# Input.net
KiCad netlist of a schematic drawn in Altium Designer
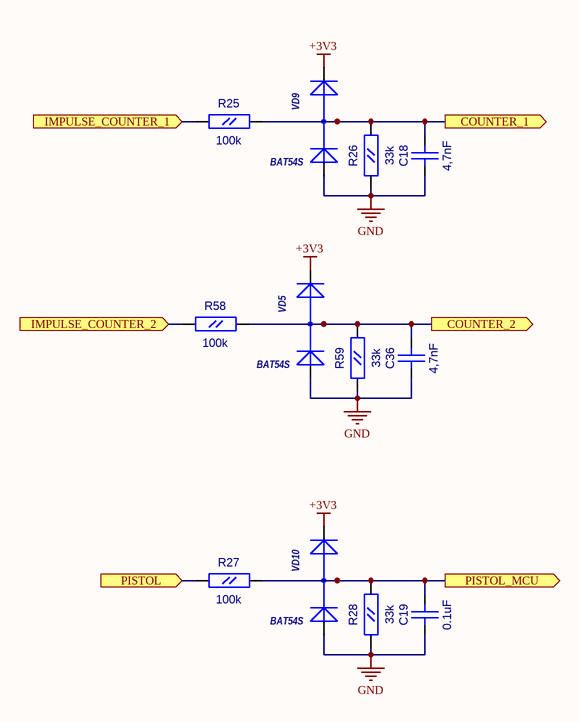
[diagram p0: Input.SchDoc]

(export (version "E")
  (design (tool "Eeschema 10.0.6"))
  (components
    (comp (ref "C18")
      (value "4,7nF")
      (footprint "CC0603")
      (description "CC0603")
      (libsource (lib "gprs_modem_2") (part "CC0603"))
    )
    (comp (ref "C19")
      (value "0.1uF")
      (footprint "CC0603")
      (description "CC0603")
      (libsource (lib "gprs_modem_2") (part "CC0603"))
    )
    (comp (ref "C36")
      (value "4,7nF")
      (footprint "CC0603")
      (description "CC0603")
      (libsource (lib "gprs_modem_2") (part "CC0603"))
    )
    (comp (ref "R25")
      (value "100k")
      (footprint "RC0603")
      (description "RC0603")
      (libsource (lib "gprs_modem_2") (part "RC0603"))
    )
    (comp (ref "R26")
      (value "33k")
      (footprint "RC0603")
      (description "RC0603")
      (libsource (lib "gprs_modem_2") (part "RC0603"))
    )
    (comp (ref "R27")
      (value "100k")
      (footprint "RC0603")
      (description "RC0603")
      (libsource (lib "gprs_modem_2") (part "RC0603"))
    )
    (comp (ref "R28")
      (value "33k")
      (footprint "RC0603")
      (description "RC0603")
      (libsource (lib "gprs_modem_2") (part "RC0603"))
    )
    (comp (ref "R58")
      (value "100k")
      (footprint "RC0603")
      (description "RC0603")
      (libsource (lib "gprs_modem_2") (part "RC0603"))
    )
    (comp (ref "R59")
      (value "33k")
      (footprint "RC0603")
      (description "RC0603")
      (libsource (lib "gprs_modem_2") (part "RC0603"))
    )
    (comp (ref "VD5")
      (value "BAT54S")
      (footprint "SOT-23(GSD)")
      (description "1.0 Ampere General Purpose Rectifier")
      (libsource (lib "gprs_modem_2") (part "BAT54S"))
    )
    (comp (ref "VD9")
      (value "BAT54S")
      (footprint "SOT-23(GSD)")
      (description "1.0 Ampere General Purpose Rectifier")
      (libsource (lib "gprs_modem_2") (part "BAT54S"))
    )
    (comp (ref "VD10")
      (value "BAT54S")
      (footprint "SOT-23(GSD)")
      (description "1.0 Ampere General Purpose Rectifier")
      (libsource (lib "gprs_modem_2") (part "BAT54S"))
    )
  )
  (nets
    (net (code "1") (name "+3V3") (class "Default")
      (node (ref "VD10") (pin "2") (pinfunction "K_2") (pintype "passive"))
      (node (ref "VD5") (pin "2") (pinfunction "K_2") (pintype "passive"))
      (node (ref "VD9") (pin "2") (pinfunction "K_2") (pintype "passive"))
    )
    (net (code "2") (name "/COUNTER_1") (class "Default")
      (node (ref "C18") (pin "2") (pinfunction "B_2") (pintype "passive"))
      (node (ref "R25") (pin "2") (pinfunction "B_2") (pintype "passive"))
      (node (ref "R26") (pin "2") (pinfunction "B_2") (pintype "passive"))
      (node (ref "VD9") (pin "3") (pinfunction "AK_3") (pintype "passive"))
    )
    (net (code "3") (name "/COUNTER_2") (class "Default")
      (node (ref "C36") (pin "2") (pinfunction "B_2") (pintype "passive"))
      (node (ref "R58") (pin "2") (pinfunction "B_2") (pintype "passive"))
      (node (ref "R59") (pin "2") (pinfunction "B_2") (pintype "passive"))
      (node (ref "VD5") (pin "3") (pinfunction "AK_3") (pintype "passive"))
    )
    (net (code "4") (name "/IMPULSE_COUNTER_1") (class "Default")
      (node (ref "R25") (pin "1") (pinfunction "A_1") (pintype "passive"))
    )
    (net (code "5") (name "/IMPULSE_COUNTER_2") (class "Default")
      (node (ref "R58") (pin "1") (pinfunction "A_1") (pintype "passive"))
    )
    (net (code "6") (name "/PISTOL") (class "Default")
      (node (ref "R27") (pin "1") (pinfunction "A_1") (pintype "passive"))
    )
    (net (code "7") (name "/PISTOL_MCU") (class "Default")
      (node (ref "C19") (pin "2") (pinfunction "B_2") (pintype "passive"))
      (node (ref "R27") (pin "2") (pinfunction "B_2") (pintype "passive"))
      (node (ref "R28") (pin "2") (pinfunction "B_2") (pintype "passive"))
      (node (ref "VD10") (pin "3") (pinfunction "AK_3") (pintype "passive"))
    )
    (net (code "8") (name "GND") (class "Default")
      (node (ref "C18") (pin "1") (pinfunction "A_1") (pintype "passive"))
      (node (ref "C19") (pin "1") (pinfunction "A_1") (pintype "passive"))
      (node (ref "C36") (pin "1") (pinfunction "A_1") (pintype "passive"))
      (node (ref "R26") (pin "1") (pinfunction "A_1") (pintype "passive"))
      (node (ref "R28") (pin "1") (pinfunction "A_1") (pintype "passive"))
      (node (ref "R59") (pin "1") (pinfunction "A_1") (pintype "passive"))
      (node (ref "VD10") (pin "1") (pinfunction "A_1") (pintype "passive"))
      (node (ref "VD5") (pin "1") (pinfunction "A_1") (pintype "passive"))
      (node (ref "VD9") (pin "1") (pinfunction "A_1") (pintype "passive"))
    )
  )
)
